# sunface.net
KiCad netlist of a schematic drawn in EAGLE
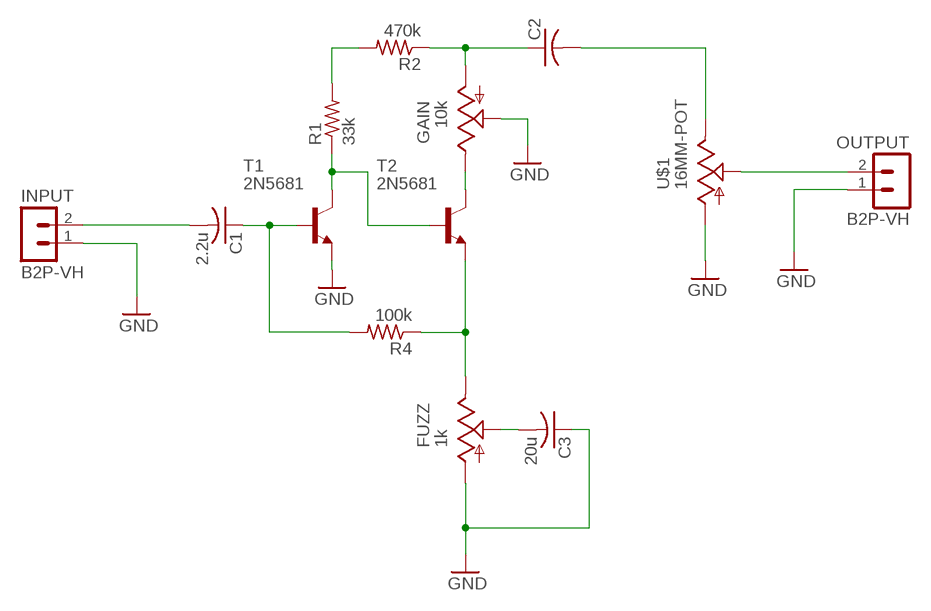
[diagram p0: schematic, sheet 1]

(export (version "E")
  (design (tool "Eeschema 10.0.6"))
  (components
    (comp (ref "C1")
      (value "2.2u")
      (footprint "eagle-import:C050-045X075")
      (libsource (lib "eagle-import") (part "C-US050-045X075"))
    )
    (comp (ref "C2")
      (value "C-US050-045X075")
      (footprint "eagle-import:C050-045X075")
      (libsource (lib "eagle-import") (part "C-US050-045X075"))
    )
    (comp (ref "C3")
      (value "20u")
      (footprint "eagle-import:C050-045X075")
      (libsource (lib "eagle-import") (part "C-US050-045X075"))
    )
    (comp (ref "FUZZ")
      (value "1k")
      (footprint "eagle-import:ALPHA-16-MINI")
      (libsource (lib "eagle-import") (part "16MM-POT"))
    )
    (comp (ref "GAIN")
      (value "10k")
      (footprint "eagle-import:ALPHA-16-MINI")
      (libsource (lib "eagle-import") (part "16MM-POT"))
    )
    (comp (ref "INPUT")
      (value "B2P-VH")
      (footprint "eagle-import:B2P-VH")
      (libsource (lib "eagle-import") (part "B2P-VH"))
    )
    (comp (ref "OUTPUT")
      (value "B2P-VH")
      (footprint "eagle-import:B2P-VH")
      (libsource (lib "eagle-import") (part "B2P-VH"))
    )
    (comp (ref "R1")
      (value "33k")
      (footprint "eagle-import:0411_15")
      (libsource (lib "eagle-import") (part "R-US_0411/15"))
    )
    (comp (ref "R2")
      (value "470k")
      (footprint "eagle-import:0411_15")
      (libsource (lib "eagle-import") (part "R-US_0411/15"))
    )
    (comp (ref "R4")
      (value "100k")
      (footprint "eagle-import:0411_15")
      (libsource (lib "eagle-import") (part "R-US_0411/15"))
    )
    (comp (ref "T1")
      (value "2N5681")
      (footprint "eagle-import:TO5")
      (libsource (lib "eagle-import") (part "2N5681"))
    )
    (comp (ref "T2")
      (value "2N5681")
      (footprint "eagle-import:TO5")
      (libsource (lib "eagle-import") (part "2N5681"))
    )
    (comp (ref "U$1")
      (value "16MM-POT")
      (footprint "eagle-import:ALPHA-16-MINI")
      (libsource (lib "eagle-import") (part "16MM-POT"))
    )
  )
  (nets
    (net (code "1") (name "GND") (class "Default")
      (node (ref "C3") (pin "1") (pinfunction "1_1") (pintype "passive"))
      (node (ref "FUZZ") (pin "LEFT") (pinfunction "LEFT_LEFT") (pintype "passive"))
      (node (ref "GAIN") (pin "WIPER") (pinfunction "WIPER_WIPER") (pintype "passive"))
      (node (ref "INPUT") (pin "1") (pinfunction "1_1") (pintype "passive"))
      (node (ref "OUTPUT") (pin "1") (pinfunction "1_1") (pintype "passive"))
      (node (ref "T1") (pin "1") (pinfunction "E_1") (pintype "passive"))
      (node (ref "U$1") (pin "LEFT") (pinfunction "LEFT_LEFT") (pintype "passive"))
    )
    (net (code "2") (name "Net-(C1-Pad2)") (class "Default")
      (node (ref "C1") (pin "2") (pinfunction "2_2") (pintype "passive"))
      (node (ref "INPUT") (pin "2") (pinfunction "2_2") (pintype "passive"))
    )
    (net (code "3") (name "Net-(C2-Pad1)") (class "Default")
      (node (ref "C2") (pin "1") (pinfunction "1_1") (pintype "passive"))
      (node (ref "GAIN") (pin "LEFT") (pinfunction "LEFT_LEFT") (pintype "passive"))
      (node (ref "R2") (pin "1") (pinfunction "1_1") (pintype "passive"))
    )
    (net (code "4") (name "Net-(C2-Pad2)") (class "Default")
      (node (ref "C2") (pin "2") (pinfunction "2_2") (pintype "passive"))
      (node (ref "U$1") (pin "RIGHT") (pinfunction "RIGHT_RIGHT") (pintype "passive"))
    )
    (net (code "5") (name "Net-(C3-Pad2)") (class "Default")
      (node (ref "C3") (pin "2") (pinfunction "2_2") (pintype "passive"))
      (node (ref "FUZZ") (pin "WIPER") (pinfunction "WIPER_WIPER") (pintype "passive"))
    )
    (net (code "6") (name "Net-(OUTPUT-Pad2)") (class "Default")
      (node (ref "OUTPUT") (pin "2") (pinfunction "2_2") (pintype "passive"))
      (node (ref "U$1") (pin "WIPER") (pinfunction "WIPER_WIPER") (pintype "passive"))
    )
    (net (code "7") (name "Net-(R1-Pad2)") (class "Default")
      (node (ref "R1") (pin "2") (pinfunction "2_2") (pintype "passive"))
      (node (ref "R2") (pin "2") (pinfunction "2_2") (pintype "passive"))
    )
    (net (code "8") (name "Net-(T1-B)") (class "Default")
      (node (ref "C1") (pin "1") (pinfunction "1_1") (pintype "passive"))
      (node (ref "R4") (pin "2") (pinfunction "2_2") (pintype "passive"))
      (node (ref "T1") (pin "2") (pinfunction "B_2") (pintype "passive"))
    )
    (net (code "9") (name "Net-(T1-C)") (class "Default")
      (node (ref "R1") (pin "1") (pinfunction "1_1") (pintype "passive"))
      (node (ref "T1") (pin "3") (pinfunction "C_3") (pintype "passive"))
      (node (ref "T2") (pin "2") (pinfunction "B_2") (pintype "passive"))
    )
    (net (code "10") (name "Net-(T2-C)") (class "Default")
      (node (ref "GAIN") (pin "RIGHT") (pinfunction "RIGHT_RIGHT") (pintype "passive"))
      (node (ref "T2") (pin "3") (pinfunction "C_3") (pintype "passive"))
    )
    (net (code "11") (name "Net-(T2-E)") (class "Default")
      (node (ref "FUZZ") (pin "RIGHT") (pinfunction "RIGHT_RIGHT") (pintype "passive"))
      (node (ref "R4") (pin "1") (pinfunction "1_1") (pintype "passive"))
      (node (ref "T2") (pin "1") (pinfunction "E_1") (pintype "passive"))
    )
  )
)
